# LNA-N.net
KiCad netlist of a schematic drawn in EAGLE
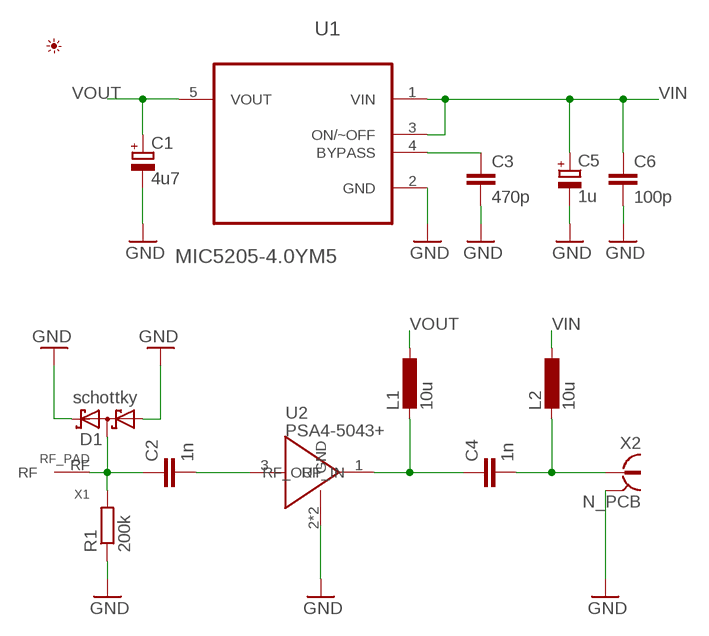
[diagram p0: schematic, sheet 1]

(export (version "E")
  (design (tool "Eeschema 10.0.6"))
  (components
    (comp (ref "C1")
      (value "4u7")
      (footprint "eagle-import:SMC_A")
      (libsource (lib "eagle-import") (part "CPOL-EUSMCA"))
    )
    (comp (ref "C2")
      (value "1n")
      (footprint "eagle-import:C0805")
      (libsource (lib "eagle-import") (part "C-EUC0805"))
    )
    (comp (ref "C3")
      (value "470p")
      (footprint "eagle-import:C0603")
      (libsource (lib "eagle-import") (part "C-EUC0603"))
    )
    (comp (ref "C4")
      (value "1n")
      (footprint "eagle-import:C0805")
      (libsource (lib "eagle-import") (part "C-EUC0805"))
    )
    (comp (ref "C5")
      (value "1u")
      (footprint "eagle-import:SMC_A")
      (libsource (lib "eagle-import") (part "CPOL-EUSMCA"))
    )
    (comp (ref "C6")
      (value "100p")
      (footprint "eagle-import:C0603")
      (libsource (lib "eagle-import") (part "C-EUC0603"))
    )
    (comp (ref "D1")
      (value "schottky")
      (footprint "eagle-import:SOT23")
      (libsource (lib "eagle-import") (part "BAS70-04"))
    )
    (comp (ref "L1")
      (value "10u")
      (footprint "eagle-import:L2012C")
      (libsource (lib "eagle-import") (part "L-EUL2012C"))
    )
    (comp (ref "L2")
      (value "10u")
      (footprint "eagle-import:L2012C")
      (libsource (lib "eagle-import") (part "L-EUL2012C"))
    )
    (comp (ref "R1")
      (value "200k")
      (footprint "eagle-import:R0805")
      (libsource (lib "eagle-import") (part "R-EU_R0805"))
    )
    (comp (ref "U$1")
      (value "PICTO_1")
      (footprint "eagle-import:PICTO_1")
      (libsource (lib "eagle-import") (part "PICTO_1"))
    )
    (comp (ref "U1")
      (value "MIC5205-4.0YM5")
      (footprint "eagle-import:SOT95P280X145-5N")
      (fields (field (name "MPN") "LP2985A-18DBVJ"))
      (libsource (lib "eagle-import") (part "LP2985A-18DBVJ"))
    )
    (comp (ref "U2")
      (value "PSA4-5043+")
      (footprint "eagle-import:SOT343")
      (libsource (lib "eagle-import") (part "PSA4-5043+"))
    )
    (comp (ref "X1")
      (value "RF_PAD")
      (footprint "eagle-import:RF_PAD")
      (libsource (lib "eagle-import") (part "RF_PAD"))
    )
    (comp (ref "X2")
      (value "N_PCB")
      (footprint "eagle-import:N_PCB")
      (libsource (lib "eagle-import") (part "N_PCB"))
    )
  )
  (nets
    (net (code "1") (name "/VIN") (class "Default")
      (node (ref "C5") (pin "+") (pinfunction "+_+") (pintype "passive"))
      (node (ref "C6") (pin "1") (pinfunction "1_1") (pintype "passive"))
      (node (ref "L2") (pin "1") (pinfunction "1_1") (pintype "passive"))
      (node (ref "U1") (pin "1") (pinfunction "VIN_1") (pintype "input"))
      (node (ref "U1") (pin "3") (pinfunction "ON/~{OFF}_3") (pintype "input"))
    )
    (net (code "2") (name "/VOUT") (class "Default")
      (node (ref "C1") (pin "+") (pinfunction "+_+") (pintype "passive"))
      (node (ref "L1") (pin "1") (pinfunction "1_1") (pintype "passive"))
      (node (ref "U1") (pin "5") (pinfunction "VOUT_5") (pintype "output"))
    )
    (net (code "3") (name "GND") (class "Default")
      (node (ref "C1") (pin "-") (pinfunction "-_-") (pintype "passive"))
      (node (ref "C3") (pin "2") (pinfunction "2_2") (pintype "passive"))
      (node (ref "C5") (pin "-") (pinfunction "-_-") (pintype "passive"))
      (node (ref "C6") (pin "2") (pinfunction "2_2") (pintype "passive"))
      (node (ref "D1") (pin "1") (pinfunction "A1_1") (pintype "passive"))
      (node (ref "D1") (pin "2") (pinfunction "C2_2") (pintype "passive"))
      (node (ref "R1") (pin "1") (pinfunction "1_1") (pintype "passive"))
      (node (ref "U1") (pin "2") (pinfunction "GND_2") (pintype "passive"))
      (node (ref "U2") (pin "2") (pinfunction "GND_2") (pintype "power_in"))
      (node (ref "U2") (pin "4") (pinfunction "GND_4") (pintype "power_in"))
      (node (ref "X2") (pin "2") (pinfunction "2_2") (pintype "passive"))
      (node (ref "X2") (pin "3") (pinfunction "2_3") (pintype "passive"))
      (node (ref "X2") (pin "4") (pinfunction "2_4") (pintype "passive"))
      (node (ref "X2") (pin "5") (pinfunction "2_5") (pintype "passive"))
    )
    (net (code "4") (name "Net-(C4-Pad2)") (class "Default")
      (node (ref "C4") (pin "2") (pinfunction "2_2") (pintype "passive"))
      (node (ref "L2") (pin "2") (pinfunction "2_2") (pintype "passive"))
      (node (ref "X2") (pin "1") (pinfunction "1_1") (pintype "passive"))
    )
    (net (code "5") (name "Net-(D1-C1A2)") (class "Default")
      (node (ref "C2") (pin "1") (pinfunction "1_1") (pintype "passive"))
      (node (ref "D1") (pin "3") (pinfunction "C1A2_3") (pintype "passive"))
      (node (ref "R1") (pin "2") (pinfunction "2_2") (pintype "passive"))
      (node (ref "X1") (pin "RF") (pinfunction "RF_RF") (pintype "bidirectional"))
    )
    (net (code "6") (name "Net-(U1-BYPASS)") (class "Default")
      (node (ref "C3") (pin "1") (pinfunction "1_1") (pintype "passive"))
      (node (ref "U1") (pin "4") (pinfunction "BYPASS_4") (pintype "input"))
    )
    (net (code "7") (name "Net-(U2-RF_IN)") (class "Default")
      (node (ref "C2") (pin "2") (pinfunction "2_2") (pintype "passive"))
      (node (ref "U2") (pin "3") (pinfunction "RF_IN_3") (pintype "input"))
    )
    (net (code "8") (name "Net-(U2-RF_OUT)") (class "Default")
      (node (ref "C4") (pin "1") (pinfunction "1_1") (pintype "passive"))
      (node (ref "L1") (pin "2") (pinfunction "2_2") (pintype "passive"))
      (node (ref "U2") (pin "1") (pinfunction "RF_OUT_1") (pintype "output"))
    )
  )
)
